# compressor_contro0l.net
KiCad netlist of a schematic drawn in EAGLE
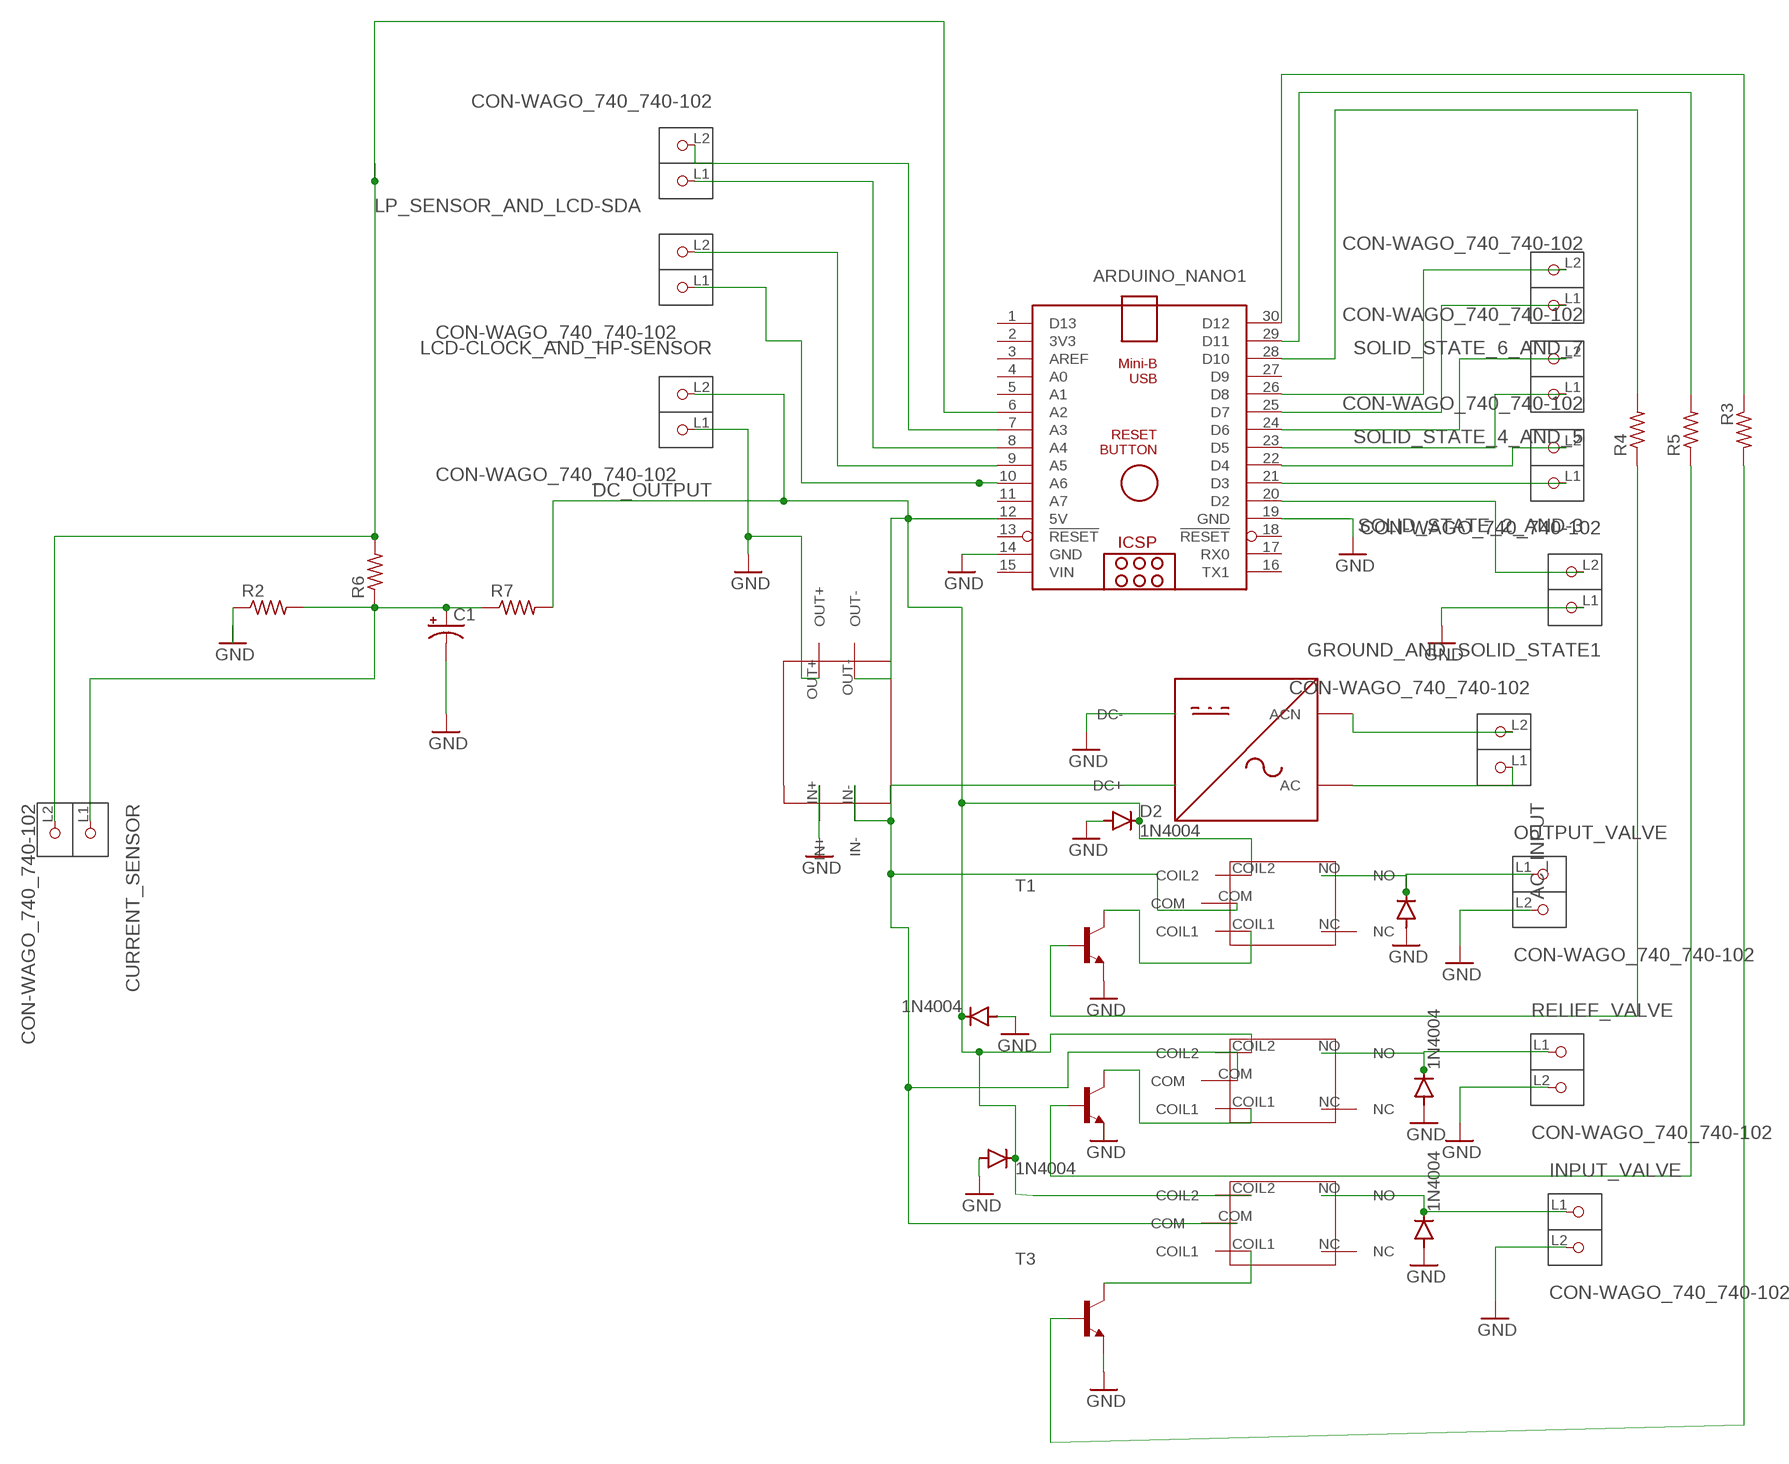
[diagram p0: schematic, sheet 1]

(export (version "E")
  (design (tool "Eeschema 10.0.6"))
  (components
    (comp (ref "AC-DC_12V-OUTPUT")
      (value "RPD10W1S")
      (footprint "eagle-import:2343")
      (libsource (lib "eagle-import") (part "RPD10W1S"))
    )
    (comp (ref "AC_INPUT")
      (value "CON-WAGO_740_740-102")
      (footprint "eagle-import:CON-WAGO_740_P-740-102")
      (libsource (lib "eagle-import") (part "CON-WAGO_740_740-102"))
    )
    (comp (ref "ARDUINO_NANO1")
      (value "ARDUINONANOV30-GHIT_ARDUINO_NANO")
      (footprint "eagle-import:ARDUINONANOV30-GHIT_ARDUINO_NANO")
      (libsource (lib "eagle-import") (part "ARDUINONANOV30-GHIT_ARDUINO_NANO"))
    )
    (comp (ref "C1")
      (value "CPOL-USE3.5-8")
      (footprint "eagle-import:E3,5-8")
      (libsource (lib "eagle-import") (part "CPOL-USE3.5-8"))
    )
    (comp (ref "CURRENT_SENSOR")
      (value "CON-WAGO_740_740-102")
      (footprint "eagle-import:CON-WAGO_740_P-740-102")
      (libsource (lib "eagle-import") (part "CON-WAGO_740_740-102"))
    )
    (comp (ref "D2")
      (value "1N4004")
      (footprint "eagle-import:DO41-10")
      (libsource (lib "eagle-import") (part "1N4004"))
    )
    (comp (ref "D3")
      (value "1N4004")
      (footprint "eagle-import:DO41-10")
      (libsource (lib "eagle-import") (part "1N4004"))
    )
    (comp (ref "D4")
      (value "1N4004")
      (footprint "eagle-import:DO41-10")
      (libsource (lib "eagle-import") (part "1N4004"))
    )
    (comp (ref "D5")
      (value "1N4004")
      (footprint "eagle-import:DO41-10")
      (libsource (lib "eagle-import") (part "1N4004"))
    )
    (comp (ref "D6")
      (value "1N4004")
      (footprint "eagle-import:DO41-10")
      (libsource (lib "eagle-import") (part "1N4004"))
    )
    (comp (ref "D7")
      (value "1N4004")
      (footprint "eagle-import:DO41-10")
      (libsource (lib "eagle-import") (part "1N4004"))
    )
    (comp (ref "DC-DC_BUCK-CONVERTOR")
      (value "DC-DCBUCK")
      (footprint "eagle-import:DC-DCBUCK")
      (libsource (lib "eagle-import") (part "DC-DCBUCK"))
    )
    (comp (ref "DC_OUTPUT")
      (value "CON-WAGO_740_740-102")
      (footprint "eagle-import:CON-WAGO_740_P-740-102")
      (libsource (lib "eagle-import") (part "CON-WAGO_740_740-102"))
    )
    (comp (ref "GROUND_AND_SOLID_STATE1")
      (value "CON-WAGO_740_740-102")
      (footprint "eagle-import:CON-WAGO_740_P-740-102")
      (libsource (lib "eagle-import") (part "CON-WAGO_740_740-102"))
    )
    (comp (ref "INPUT_VALVE")
      (value "CON-WAGO_740_740-102")
      (footprint "eagle-import:CON-WAGO_740_P-740-102")
      (libsource (lib "eagle-import") (part "CON-WAGO_740_740-102"))
    )
    (comp (ref "INTAKE-VALVE_RELAY")
      (value "MRELAY2MRELAY2")
      (footprint "eagle-import:MRELAY")
      (libsource (lib "eagle-import") (part "MRELAY2MRELAY2"))
    )
    (comp (ref "LCD-CLOCK_AND_HP-SENSOR")
      (value "CON-WAGO_740_740-102")
      (footprint "eagle-import:CON-WAGO_740_P-740-102")
      (libsource (lib "eagle-import") (part "CON-WAGO_740_740-102"))
    )
    (comp (ref "LP_SENSOR_AND_LCD-SDA")
      (value "CON-WAGO_740_740-102")
      (footprint "eagle-import:CON-WAGO_740_P-740-102")
      (libsource (lib "eagle-import") (part "CON-WAGO_740_740-102"))
    )
    (comp (ref "OUTPUT-VALVE_RELAY")
      (value "MRELAY2MRELAY2")
      (footprint "eagle-import:MRELAY")
      (libsource (lib "eagle-import") (part "MRELAY2MRELAY2"))
    )
    (comp (ref "OUTPUT_VALVE")
      (value "CON-WAGO_740_740-102")
      (footprint "eagle-import:CON-WAGO_740_P-740-102")
      (libsource (lib "eagle-import") (part "CON-WAGO_740_740-102"))
    )
    (comp (ref "R2")
      (value "R-US_0207/10")
      (footprint "eagle-import:0207_10")
      (libsource (lib "eagle-import") (part "rcl_334_R-US_0207/10"))
    )
    (comp (ref "R3")
      (value "R-US_0613/15")
      (footprint "eagle-import:P0613_15")
      (libsource (lib "eagle-import") (part "R-US_0613/15"))
    )
    (comp (ref "R4")
      (value "R-US_0613/15")
      (footprint "eagle-import:P0613_15")
      (libsource (lib "eagle-import") (part "R-US_0613/15"))
    )
    (comp (ref "R5")
      (value "R-US_0613/15")
      (footprint "eagle-import:P0613_15")
      (libsource (lib "eagle-import") (part "R-US_0613/15"))
    )
    (comp (ref "R6")
      (value "R-US_0207/10")
      (footprint "eagle-import:0207_10")
      (libsource (lib "eagle-import") (part "rcl_334_R-US_0207/10"))
    )
    (comp (ref "R7")
      (value "R-US_0207/10")
      (footprint "eagle-import:0207_10")
      (libsource (lib "eagle-import") (part "rcl_334_R-US_0207/10"))
    )
    (comp (ref "RELIEF-VALVE_RELAY")
      (value "MRELAY2MRELAY2")
      (footprint "eagle-import:MRELAY")
      (libsource (lib "eagle-import") (part "MRELAY2MRELAY2"))
    )
    (comp (ref "RELIEF_VALVE")
      (value "CON-WAGO_740_740-102")
      (footprint "eagle-import:CON-WAGO_740_P-740-102")
      (libsource (lib "eagle-import") (part "CON-WAGO_740_740-102"))
    )
    (comp (ref "SOLID_STATE_2_AND-3")
      (value "CON-WAGO_740_740-102")
      (footprint "eagle-import:CON-WAGO_740_P-740-102")
      (libsource (lib "eagle-import") (part "CON-WAGO_740_740-102"))
    )
    (comp (ref "SOLID_STATE_4_AND_5")
      (value "CON-WAGO_740_740-102")
      (footprint "eagle-import:CON-WAGO_740_P-740-102")
      (libsource (lib "eagle-import") (part "CON-WAGO_740_740-102"))
    )
    (comp (ref "SOLID_STATE_6_AND_7")
      (value "CON-WAGO_740_740-102")
      (footprint "eagle-import:CON-WAGO_740_P-740-102")
      (libsource (lib "eagle-import") (part "CON-WAGO_740_740-102"))
    )
    (comp (ref "T1")
      (value "2N2222-NPN-TO92-EBC")
      (footprint "eagle-import:TO92-EBC")
      (libsource (lib "eagle-import") (part "-NPN-TO92-EBC2N2222"))
    )
    (comp (ref "T2")
      (value "2N2222-NPN-TO92-EBC")
      (footprint "eagle-import:TO92-EBC")
      (libsource (lib "eagle-import") (part "-NPN-TO92-EBC2N2222"))
    )
    (comp (ref "T3")
      (value "2N2222-NPN-TO92-EBC")
      (footprint "eagle-import:TO92-EBC")
      (libsource (lib "eagle-import") (part "-NPN-TO92-EBC2N2222"))
    )
  )
  (nets
    (net (code "1") (name "/VIN") (class "Default")
      (node (ref "ARDUINO_NANO1") (pin "15") (pinfunction "VIN_15") (pintype "power_in"))
    )
    (net (code "2") (name "GND") (class "Default")
      (node (ref "AC-DC_12V-OUTPUT") (pin "DC-") (pinfunction "DC-_DC-") (pintype "bidirectional"))
      (node (ref "ARDUINO_NANO1") (pin "14") (pinfunction "GND_14") (pintype "power_in"))
      (node (ref "ARDUINO_NANO1") (pin "19") (pinfunction "GND_19") (pintype "power_in"))
      (node (ref "C1") (pin "-") (pinfunction "-_-") (pintype "passive"))
      (node (ref "D2") (pin "A") (pinfunction "A_A") (pintype "passive"))
      (node (ref "D3") (pin "A") (pinfunction "A_A") (pintype "passive"))
      (node (ref "D4") (pin "A") (pinfunction "A_A") (pintype "passive"))
      (node (ref "D5") (pin "A") (pinfunction "A_A") (pintype "passive"))
      (node (ref "D6") (pin "A") (pinfunction "A_A") (pintype "passive"))
      (node (ref "D7") (pin "A") (pinfunction "A_A") (pintype "passive"))
      (node (ref "DC-DC_BUCK-CONVERTOR") (pin "IN+") (pinfunction "IN+_IN+") (pintype "bidirectional"))
      (node (ref "DC-DC_BUCK-CONVERTOR") (pin "OUT+") (pinfunction "OUT+_OUT+") (pintype "bidirectional"))
      (node (ref "DC_OUTPUT") (pin "L1") (pinfunction "P1_L1") (pintype "bidirectional"))
      (node (ref "GROUND_AND_SOLID_STATE1") (pin "L1") (pinfunction "P1_L1") (pintype "bidirectional"))
      (node (ref "INPUT_VALVE") (pin "L2") (pinfunction "P2_L2") (pintype "bidirectional"))
      (node (ref "OUTPUT_VALVE") (pin "L2") (pinfunction "P2_L2") (pintype "bidirectional"))
      (node (ref "R2") (pin "1") (pinfunction "1_1") (pintype "passive"))
      (node (ref "RELIEF_VALVE") (pin "L2") (pinfunction "P2_L2") (pintype "bidirectional"))
      (node (ref "T1") (pin "E") (pinfunction "E_E") (pintype "passive"))
      (node (ref "T2") (pin "E") (pinfunction "E_E") (pintype "passive"))
      (node (ref "T3") (pin "E") (pinfunction "E_E") (pintype "passive"))
    )
    (net (code "3") (name "Net-(AC-DC_12V-OUTPUT-PadDC+)") (class "Default")
      (node (ref "AC-DC_12V-OUTPUT") (pin "DC+") (pinfunction "DC+_DC+") (pintype "bidirectional"))
      (node (ref "DC-DC_BUCK-CONVERTOR") (pin "IN-") (pinfunction "IN-_IN-") (pintype "bidirectional"))
      (node (ref "INTAKE-VALVE_RELAY") (pin "COM") (pinfunction "COM_COM") (pintype "bidirectional"))
      (node (ref "OUTPUT-VALVE_RELAY") (pin "COM") (pinfunction "COM_COM") (pintype "bidirectional"))
      (node (ref "RELIEF-VALVE_RELAY") (pin "COM") (pinfunction "COM_COM") (pintype "bidirectional"))
    )
    (net (code "4") (name "Net-(AC_INPUT-P1)") (class "Default")
      (node (ref "AC-DC_12V-OUTPUT") (pin "AC") (pinfunction "AC_AC") (pintype "bidirectional"))
      (node (ref "AC_INPUT") (pin "L1") (pinfunction "P1_L1") (pintype "bidirectional"))
    )
    (net (code "5") (name "Net-(AC_INPUT-P2)") (class "Default")
      (node (ref "AC-DC_12V-OUTPUT") (pin "ACN") (pinfunction "ACN_ACN") (pintype "bidirectional"))
      (node (ref "AC_INPUT") (pin "L2") (pinfunction "P2_L2") (pintype "bidirectional"))
    )
    (net (code "6") (name "Net-(ARDUINO_NANO1-5V)") (class "Default")
      (node (ref "ARDUINO_NANO1") (pin "12") (pinfunction "5V_12") (pintype "power_in"))
      (node (ref "D2") (pin "C") (pinfunction "C_C") (pintype "passive"))
      (node (ref "D4") (pin "C") (pinfunction "C_C") (pintype "passive"))
      (node (ref "D5") (pin "C") (pinfunction "C_C") (pintype "passive"))
      (node (ref "DC-DC_BUCK-CONVERTOR") (pin "OUT-") (pinfunction "OUT-_OUT-") (pintype "bidirectional"))
      (node (ref "DC_OUTPUT") (pin "L2") (pinfunction "P2_L2") (pintype "bidirectional"))
      (node (ref "INTAKE-VALVE_RELAY") (pin "COIL2") (pinfunction "COIL2_COIL2") (pintype "bidirectional"))
      (node (ref "OUTPUT-VALVE_RELAY") (pin "COIL2") (pinfunction "COIL2_COIL2") (pintype "bidirectional"))
      (node (ref "R7") (pin "2") (pinfunction "2_2") (pintype "passive"))
      (node (ref "RELIEF-VALVE_RELAY") (pin "COIL2") (pinfunction "COIL2_COIL2") (pintype "bidirectional"))
    )
    (net (code "7") (name "Net-(ARDUINO_NANO1-A2)") (class "Default")
      (node (ref "ARDUINO_NANO1") (pin "6") (pinfunction "A2_6") (pintype "bidirectional"))
      (node (ref "CURRENT_SENSOR") (pin "L2") (pinfunction "P2_L2") (pintype "bidirectional"))
      (node (ref "R6") (pin "2") (pinfunction "2_2") (pintype "passive"))
    )
    (net (code "8") (name "Net-(ARDUINO_NANO1-A3)") (class "Default")
      (node (ref "ARDUINO_NANO1") (pin "7") (pinfunction "A3_7") (pintype "bidirectional"))
      (node (ref "LP_SENSOR_AND_LCD-SDA") (pin "L2") (pinfunction "P2_L2") (pintype "bidirectional"))
    )
    (net (code "9") (name "Net-(ARDUINO_NANO1-A4)") (class "Default")
      (node (ref "ARDUINO_NANO1") (pin "8") (pinfunction "A4_8") (pintype "bidirectional"))
      (node (ref "LP_SENSOR_AND_LCD-SDA") (pin "L1") (pinfunction "P1_L1") (pintype "bidirectional"))
    )
    (net (code "10") (name "Net-(ARDUINO_NANO1-A5)") (class "Default")
      (node (ref "ARDUINO_NANO1") (pin "9") (pinfunction "A5_9") (pintype "bidirectional"))
      (node (ref "LCD-CLOCK_AND_HP-SENSOR") (pin "L2") (pinfunction "P2_L2") (pintype "bidirectional"))
    )
    (net (code "11") (name "Net-(ARDUINO_NANO1-A6)") (class "Default")
      (node (ref "ARDUINO_NANO1") (pin "10") (pinfunction "A6_10") (pintype "bidirectional"))
      (node (ref "LCD-CLOCK_AND_HP-SENSOR") (pin "L1") (pinfunction "P1_L1") (pintype "bidirectional"))
    )
    (net (code "12") (name "Net-(ARDUINO_NANO1-D2)") (class "Default")
      (node (ref "ARDUINO_NANO1") (pin "20") (pinfunction "D2_20") (pintype "bidirectional"))
      (node (ref "GROUND_AND_SOLID_STATE1") (pin "L2") (pinfunction "P2_L2") (pintype "bidirectional"))
    )
    (net (code "13") (name "Net-(ARDUINO_NANO1-D3)") (class "Default")
      (node (ref "ARDUINO_NANO1") (pin "21") (pinfunction "D3_21") (pintype "bidirectional"))
      (node (ref "SOLID_STATE_2_AND-3") (pin "L1") (pinfunction "P1_L1") (pintype "bidirectional"))
    )
    (net (code "14") (name "Net-(ARDUINO_NANO1-D4)") (class "Default")
      (node (ref "ARDUINO_NANO1") (pin "22") (pinfunction "D4_22") (pintype "bidirectional"))
      (node (ref "SOLID_STATE_2_AND-3") (pin "L2") (pinfunction "P2_L2") (pintype "bidirectional"))
    )
    (net (code "15") (name "Net-(ARDUINO_NANO1-D5)") (class "Default")
      (node (ref "ARDUINO_NANO1") (pin "23") (pinfunction "D5_23") (pintype "bidirectional"))
      (node (ref "SOLID_STATE_4_AND_5") (pin "L1") (pinfunction "P1_L1") (pintype "bidirectional"))
    )
    (net (code "16") (name "Net-(ARDUINO_NANO1-D6)") (class "Default")
      (node (ref "ARDUINO_NANO1") (pin "24") (pinfunction "D6_24") (pintype "bidirectional"))
      (node (ref "SOLID_STATE_4_AND_5") (pin "L2") (pinfunction "P2_L2") (pintype "bidirectional"))
    )
    (net (code "17") (name "Net-(ARDUINO_NANO1-D7)") (class "Default")
      (node (ref "ARDUINO_NANO1") (pin "25") (pinfunction "D7_25") (pintype "bidirectional"))
      (node (ref "SOLID_STATE_6_AND_7") (pin "L1") (pinfunction "P1_L1") (pintype "bidirectional"))
    )
    (net (code "18") (name "Net-(ARDUINO_NANO1-D8)") (class "Default")
      (node (ref "ARDUINO_NANO1") (pin "26") (pinfunction "D8_26") (pintype "bidirectional"))
      (node (ref "SOLID_STATE_6_AND_7") (pin "L2") (pinfunction "P2_L2") (pintype "bidirectional"))
    )
    (net (code "19") (name "Net-(ARDUINO_NANO1-D10)") (class "Default")
      (node (ref "ARDUINO_NANO1") (pin "28") (pinfunction "D10_28") (pintype "bidirectional"))
      (node (ref "R4") (pin "2") (pinfunction "2_2") (pintype "passive"))
    )
    (net (code "20") (name "Net-(ARDUINO_NANO1-D11)") (class "Default")
      (node (ref "ARDUINO_NANO1") (pin "29") (pinfunction "D11_29") (pintype "bidirectional"))
      (node (ref "R5") (pin "2") (pinfunction "2_2") (pintype "passive"))
    )
    (net (code "21") (name "Net-(ARDUINO_NANO1-D12)") (class "Default")
      (node (ref "ARDUINO_NANO1") (pin "30") (pinfunction "D12_30") (pintype "bidirectional"))
      (node (ref "R3") (pin "1") (pinfunction "1_1") (pintype "passive"))
    )
    (net (code "22") (name "Net-(CURRENT_SENSOR-P1)") (class "Default")
      (node (ref "C1") (pin "+") (pinfunction "+_+") (pintype "passive"))
      (node (ref "CURRENT_SENSOR") (pin "L1") (pinfunction "P1_L1") (pintype "bidirectional"))
      (node (ref "R2") (pin "2") (pinfunction "2_2") (pintype "passive"))
      (node (ref "R6") (pin "1") (pinfunction "1_1") (pintype "passive"))
      (node (ref "R7") (pin "1") (pinfunction "1_1") (pintype "passive"))
    )
    (net (code "23") (name "Net-(INPUT_VALVE-P1)") (class "Default")
      (node (ref "D7") (pin "C") (pinfunction "C_C") (pintype "passive"))
      (node (ref "INPUT_VALVE") (pin "L1") (pinfunction "P1_L1") (pintype "bidirectional"))
      (node (ref "INTAKE-VALVE_RELAY") (pin "NO") (pinfunction "NO_NO") (pintype "bidirectional"))
    )
    (net (code "24") (name "Net-(INTAKE-VALVE_RELAY-PadCOIL1)") (class "Default")
      (node (ref "INTAKE-VALVE_RELAY") (pin "COIL1") (pinfunction "COIL1_COIL1") (pintype "bidirectional"))
      (node (ref "T3") (pin "C") (pinfunction "C_C") (pintype "passive"))
    )
    (net (code "25") (name "Net-(OUTPUT-VALVE_RELAY-PadCOIL1)") (class "Default")
      (node (ref "OUTPUT-VALVE_RELAY") (pin "COIL1") (pinfunction "COIL1_COIL1") (pintype "bidirectional"))
      (node (ref "T1") (pin "C") (pinfunction "C_C") (pintype "passive"))
    )
    (net (code "26") (name "Net-(OUTPUT_VALVE-P1)") (class "Default")
      (node (ref "D6") (pin "C") (pinfunction "C_C") (pintype "passive"))
      (node (ref "OUTPUT-VALVE_RELAY") (pin "NO") (pinfunction "NO_NO") (pintype "bidirectional"))
      (node (ref "OUTPUT_VALVE") (pin "L1") (pinfunction "P1_L1") (pintype "bidirectional"))
    )
    (net (code "27") (name "Net-(R3-Pad2)") (class "Default")
      (node (ref "R3") (pin "2") (pinfunction "2_2") (pintype "passive"))
      (node (ref "T3") (pin "B") (pinfunction "B_B") (pintype "passive"))
    )
    (net (code "28") (name "Net-(R4-Pad1)") (class "Default")
      (node (ref "R4") (pin "1") (pinfunction "1_1") (pintype "passive"))
      (node (ref "T1") (pin "B") (pinfunction "B_B") (pintype "passive"))
    )
    (net (code "29") (name "Net-(R5-Pad1)") (class "Default")
      (node (ref "R5") (pin "1") (pinfunction "1_1") (pintype "passive"))
      (node (ref "T2") (pin "B") (pinfunction "B_B") (pintype "passive"))
    )
    (net (code "30") (name "Net-(RELIEF-VALVE_RELAY-PadCOIL1)") (class "Default")
      (node (ref "RELIEF-VALVE_RELAY") (pin "COIL1") (pinfunction "COIL1_COIL1") (pintype "bidirectional"))
      (node (ref "T2") (pin "C") (pinfunction "C_C") (pintype "passive"))
    )
    (net (code "31") (name "Net-(RELIEF_VALVE-P1)") (class "Default")
      (node (ref "D3") (pin "C") (pinfunction "C_C") (pintype "passive"))
      (node (ref "RELIEF-VALVE_RELAY") (pin "NO") (pinfunction "NO_NO") (pintype "bidirectional"))
      (node (ref "RELIEF_VALVE") (pin "L1") (pinfunction "P1_L1") (pintype "bidirectional"))
    )
    (net (code "32") (name "unconnected-(ARDUINO_NANO1-3V3-Pad2)") (class "Default")
      (node (ref "ARDUINO_NANO1") (pin "2") (pinfunction "3V3_2") (pintype "output"))
    )
    (net (code "33") (name "unconnected-(ARDUINO_NANO1-A0-Pad4)") (class "Default")
      (node (ref "ARDUINO_NANO1") (pin "4") (pinfunction "A0_4") (pintype "bidirectional"))
    )
    (net (code "34") (name "unconnected-(ARDUINO_NANO1-A1-Pad5)") (class "Default")
      (node (ref "ARDUINO_NANO1") (pin "5") (pinfunction "A1_5") (pintype "bidirectional"))
    )
    (net (code "35") (name "unconnected-(ARDUINO_NANO1-A7-Pad11)") (class "Default")
      (node (ref "ARDUINO_NANO1") (pin "11") (pinfunction "A7_11") (pintype "bidirectional"))
    )
    (net (code "36") (name "unconnected-(ARDUINO_NANO1-AREF-Pad3)") (class "Default")
      (node (ref "ARDUINO_NANO1") (pin "3") (pinfunction "AREF_3") (pintype "input"))
    )
    (net (code "37") (name "unconnected-(ARDUINO_NANO1-D9-Pad27)") (class "Default")
      (node (ref "ARDUINO_NANO1") (pin "27") (pinfunction "D9_27") (pintype "bidirectional"))
    )
    (net (code "38") (name "unconnected-(ARDUINO_NANO1-D13-Pad1)") (class "Default")
      (node (ref "ARDUINO_NANO1") (pin "1") (pinfunction "D13_1") (pintype "bidirectional"))
    )
    (net (code "39") (name "unconnected-(ARDUINO_NANO1-RX0-Pad17)") (class "Default")
      (node (ref "ARDUINO_NANO1") (pin "17") (pinfunction "RX0_17") (pintype "bidirectional"))
    )
    (net (code "40") (name "unconnected-(ARDUINO_NANO1-TX1-Pad16)") (class "Default")
      (node (ref "ARDUINO_NANO1") (pin "16") (pinfunction "TX1_16") (pintype "bidirectional"))
    )
    (net (code "41") (name "unconnected-(ARDUINO_NANO1-~{RESET}-Pad13)") (class "Default")
      (node (ref "ARDUINO_NANO1") (pin "13") (pinfunction "~{RESET}_13") (pintype "input"))
    )
    (net (code "42") (name "unconnected-(ARDUINO_NANO1-~{RESET}-Pad18)") (class "Default")
      (node (ref "ARDUINO_NANO1") (pin "18") (pinfunction "~{RESET}_18") (pintype "input"))
    )
    (net (code "43") (name "unconnected-(INTAKE-VALVE_RELAY-PadNC)") (class "Default")
      (node (ref "INTAKE-VALVE_RELAY") (pin "NC") (pinfunction "NC_NC") (pintype "bidirectional"))
    )
    (net (code "44") (name "unconnected-(OUTPUT-VALVE_RELAY-PadNC)") (class "Default")
      (node (ref "OUTPUT-VALVE_RELAY") (pin "NC") (pinfunction "NC_NC") (pintype "bidirectional"))
    )
    (net (code "45") (name "unconnected-(RELIEF-VALVE_RELAY-PadNC)") (class "Default")
      (node (ref "RELIEF-VALVE_RELAY") (pin "NC") (pinfunction "NC_NC") (pintype "bidirectional"))
    )
  )
)
